# Schematic.net
KiCad netlist of a schematic drawn in EasyEDA
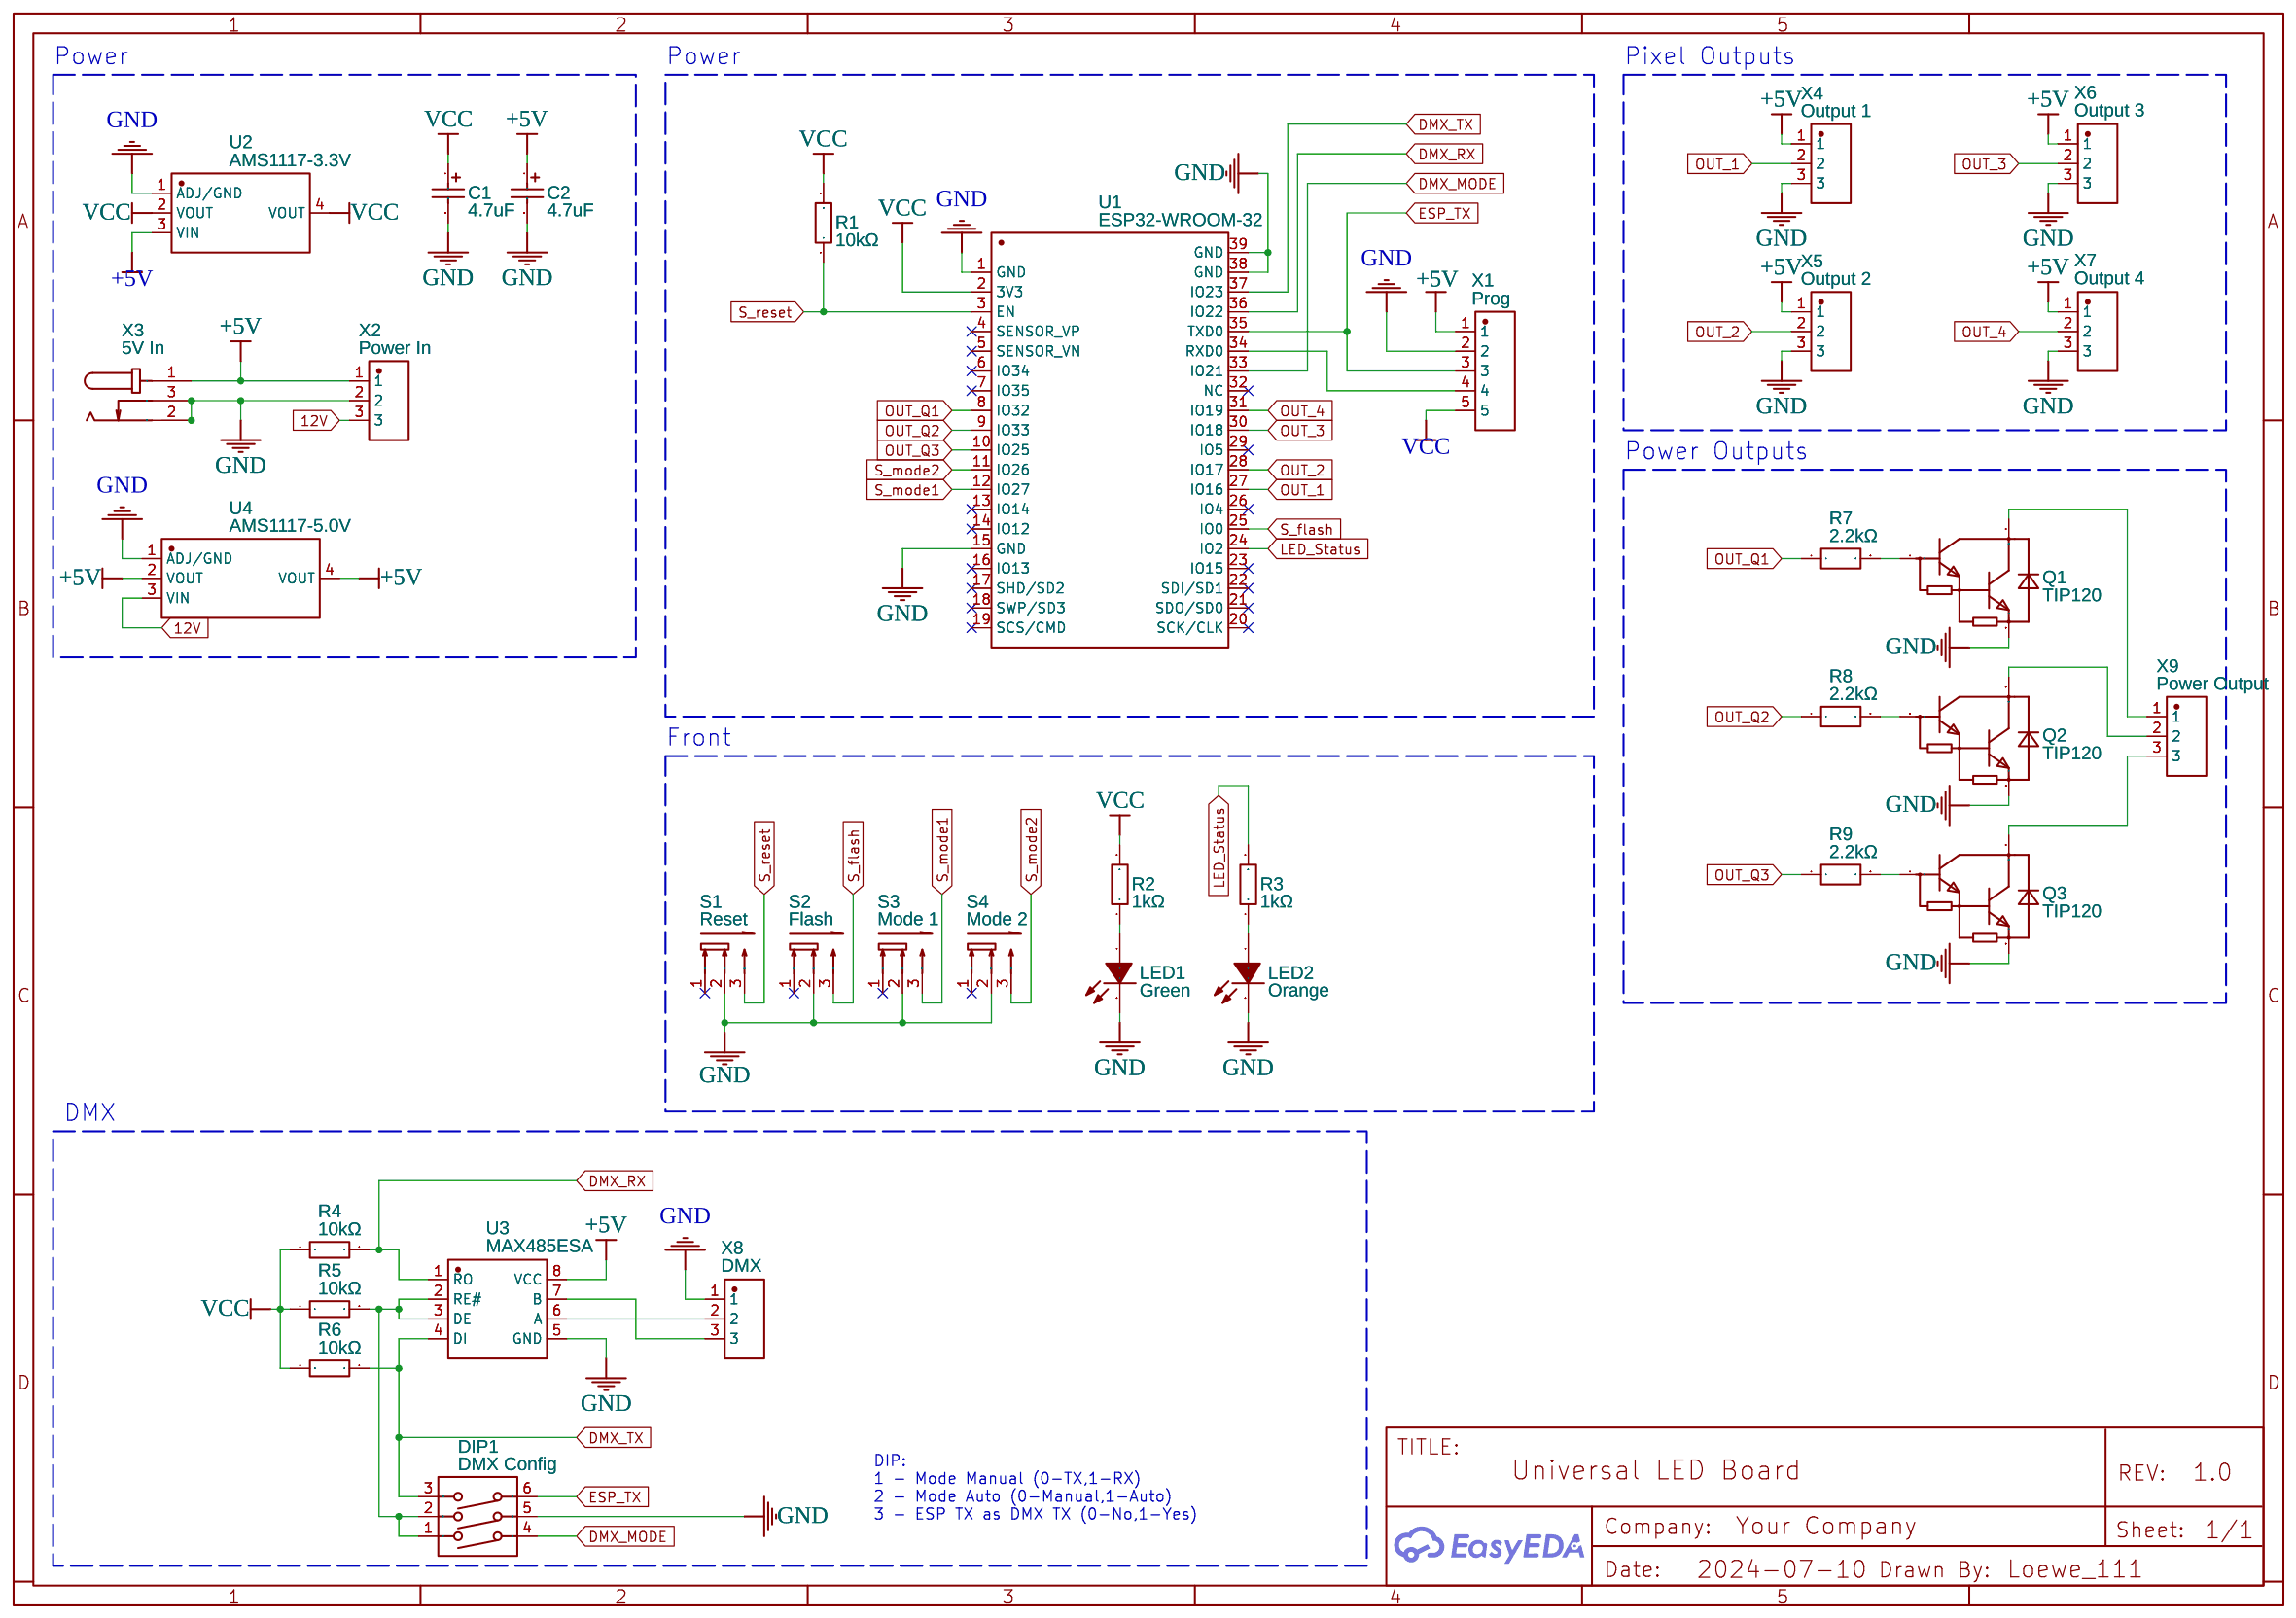
[diagram p0: schematic sheet]

(export (version "E")
  (design (tool "Eeschema 10.0.6"))
  (components
    (comp (ref "C1")
      (value "4.7uF")
      (fields
        (field (name "Manufacturer Part") "CA45-A-16V-4.7uF-K")
        (field (name "Manufacturer") "CEC(振华新云)")
      )
      (libsource (lib "") (part "CA45-A-16V-4.7UF-K"))
    )
    (comp (ref "C2")
      (value "4.7uF")
      (fields
        (field (name "Manufacturer Part") "CA45-A-16V-4.7uF-K")
        (field (name "Manufacturer") "CEC(振华新云)")
      )
      (libsource (lib "") (part "CA45-A-16V-4.7UF-K"))
    )
    (comp (ref "DIP1")
      (value "DMX Config")
      (fields (field (name "Manufacturer Part") "DSWB03LHGET") (field (name "Manufacturer") "YE"))
      (libsource (lib "") (part "DSWB03LHGET"))
    )
    (comp (ref "LED1")
      (value "Green")
      (fields (field (name "Manufacturer Part") "SZYY0603G") (field (name "Manufacturer") "yongyu(永裕光电)"))
      (libsource (lib "") (part "SZYY0603G"))
    )
    (comp (ref "LED2")
      (value "Orange")
      (fields (field (name "Manufacturer Part") "SZYY0603O") (field (name "Manufacturer") "yongyu(永裕光电)"))
      (libsource (lib "") (part "SZYY0603O"))
    )
    (comp (ref "Q1")
      (value "TIP120")
      (fields (field (name "Manufacturer") "ST(意法半导体)"))
      (libsource (lib "") (part "TIP120"))
    )
    (comp (ref "Q2")
      (value "TIP120")
      (fields (field (name "Manufacturer") "ST(意法半导体)"))
      (libsource (lib "") (part "TIP120"))
    )
    (comp (ref "Q3")
      (value "TIP120")
      (fields (field (name "Manufacturer") "ST(意法半导体)"))
      (libsource (lib "") (part "TIP120"))
    )
    (comp (ref "R1")
      (value "10kΩ")
      (fields
        (field (name "Manufacturer Part") "0603WAF1002T5E")
        (field (name "Manufacturer") "UNI-ROYAL(厚声)")
      )
      (libsource (lib "") (part "0603WAF1002T5E_2"))
    )
    (comp (ref "R2")
      (value "1kΩ")
      (fields (field (name "Manufacturer Part") "RC0603FR-071KL") (field (name "Manufacturer") "YAGEO(国巨)"))
      (libsource (lib "") (part "RC0603FR-071KL"))
    )
    (comp (ref "R3")
      (value "1kΩ")
      (fields (field (name "Manufacturer Part") "RC0603FR-071KL") (field (name "Manufacturer") "YAGEO(国巨)"))
      (libsource (lib "") (part "RC0603FR-071KL"))
    )
    (comp (ref "R4")
      (value "10kΩ")
      (fields
        (field (name "Manufacturer Part") "0603WAF1002T5E")
        (field (name "Manufacturer") "UNI-ROYAL(厚声)")
      )
      (libsource (lib "") (part "0603WAF1002T5E"))
    )
    (comp (ref "R5")
      (value "10kΩ")
      (fields
        (field (name "Manufacturer Part") "0603WAF1002T5E")
        (field (name "Manufacturer") "UNI-ROYAL(厚声)")
      )
      (libsource (lib "") (part "0603WAF1002T5E_1"))
    )
    (comp (ref "R6")
      (value "10kΩ")
      (fields
        (field (name "Manufacturer Part") "0603WAF1002T5E")
        (field (name "Manufacturer") "UNI-ROYAL(厚声)")
      )
      (libsource (lib "") (part "0603WAF1002T5E"))
    )
    (comp (ref "R7")
      (value "2.2kΩ")
      (fields (field (name "Manufacturer Part") "FRC0603J222 TS") (field (name "Manufacturer") "FOJAN(富捷)"))
      (libsource (lib "") (part "FRC0603J222 TS"))
    )
    (comp (ref "R8")
      (value "2.2kΩ")
      (fields (field (name "Manufacturer Part") "FRC0603J222 TS") (field (name "Manufacturer") "FOJAN(富捷)"))
      (libsource (lib "") (part "FRC0603J222 TS"))
    )
    (comp (ref "R9")
      (value "2.2kΩ")
      (fields (field (name "Manufacturer Part") "FRC0603J222 TS") (field (name "Manufacturer") "FOJAN(富捷)"))
      (libsource (lib "") (part "FRC0603J222 TS"))
    )
    (comp (ref "S1")
      (value "Reset")
      (fields
        (field (name "Manufacturer Part") "XKB5858-W-C")
        (field (name "Manufacturer") "XKB Connection(中国星坤)")
      )
      (libsource (lib "") (part "XKB5858-W-C"))
    )
    (comp (ref "S2")
      (value "Flash")
      (fields
        (field (name "Manufacturer Part") "XKB5858-W-C")
        (field (name "Manufacturer") "XKB Connection(中国星坤)")
      )
      (libsource (lib "") (part "XKB5858-W-C"))
    )
    (comp (ref "S3")
      (value "Mode 1")
      (fields
        (field (name "Manufacturer Part") "XKB5858-W-C")
        (field (name "Manufacturer") "XKB Connection(中国星坤)")
      )
      (libsource (lib "") (part "XKB5858-W-C"))
    )
    (comp (ref "S4")
      (value "Mode 2")
      (fields
        (field (name "Manufacturer Part") "XKB5858-W-C")
        (field (name "Manufacturer") "XKB Connection(中国星坤)")
      )
      (libsource (lib "") (part "XKB5858-W-C"))
    )
    (comp (ref "U1")
      (value "ESP32-WROOM-32")
      (fields
        (field (name "Manufacturer Part") "ESP32-WROOM-32-N4")
        (field (name "Manufacturer") "ESPRESSIF(乐鑫)")
      )
      (libsource (lib "") (part "ESP32-WROOM-32"))
    )
    (comp (ref "U2")
      (value "AMS1117-3.3V")
      (fields (field (name "Manufacturer") "WPMtek(维攀)"))
      (libsource (lib "") (part "AMS1117-3.3V"))
    )
    (comp (ref "U3")
      (value "MAX485ESA")
      (fields (field (name "Manufacturer Part") "max485ESA") (field (name "Manufacturer") "JSMSEMI(杰盛微)"))
      (libsource (lib "") (part "MAX485ESA"))
    )
    (comp (ref "U4")
      (value "AMS1117-5.0V")
      (fields (field (name "Manufacturer Part") "AMS1117-5.0") (field (name "Manufacturer") "WPMtek(维攀)"))
      (libsource (lib "") (part "AMS1117-5.0_C2909825"))
    )
    (comp (ref "X1")
      (value "Prog")
      (fields
        (field (name "Manufacturer Part") "ZX-XH2.54-5PZZ")
        (field (name "Manufacturer") "Megastar(兆星)")
      )
      (libsource (lib "") (part "ZX-XH2.54-5PZZ"))
    )
    (comp (ref "X2")
      (value "Power In")
      (fields
        (field (name "Manufacturer Part") "DB128L-5.08-3P-GN-S")
        (field (name "Manufacturer") "DORABO(地博电气)")
      )
      (libsource (lib "") (part "DB128L-5.08-3P"))
    )
    (comp (ref "X3")
      (value "5V In")
      (fields (field (name "Manufacturer Part") "DC-005-A200") (field (name "Manufacturer") "XUNPU(讯普)"))
      (libsource (lib "") (part "DC-005-A200"))
    )
    (comp (ref "X4")
      (value "Output 1")
      (fields
        (field (name "Manufacturer Part") "DB128L-5.08-3P-GN-S")
        (field (name "Manufacturer") "DORABO(地博电气)")
      )
      (libsource (lib "") (part "DB128L-5.08-3P"))
    )
    (comp (ref "X5")
      (value "Output 2")
      (fields
        (field (name "Manufacturer Part") "DB128L-5.08-3P-GN-S")
        (field (name "Manufacturer") "DORABO(地博电气)")
      )
      (libsource (lib "") (part "DB128L-5.08-3P"))
    )
    (comp (ref "X6")
      (value "Output 3")
      (fields
        (field (name "Manufacturer Part") "ZX-XH2.54-3PZZ")
        (field (name "Manufacturer") "Megastar(兆星)")
      )
      (libsource (lib "") (part "ZX-XH2.54-3PZZ"))
    )
    (comp (ref "X7")
      (value "Output 4")
      (fields
        (field (name "Manufacturer Part") "ZX-XH2.54-3PZZ")
        (field (name "Manufacturer") "Megastar(兆星)")
      )
      (libsource (lib "") (part "ZX-XH2.54-3PZZ"))
    )
    (comp (ref "X8")
      (value "DMX")
      (fields
        (field (name "Manufacturer Part") "ZX-XH2.54-3PZZ")
        (field (name "Manufacturer") "Megastar(兆星)")
      )
      (libsource (lib "") (part "ZX-XH2.54-3PZZ"))
    )
    (comp (ref "X9")
      (value "Power Output")
      (fields
        (field (name "Manufacturer Part") "DB128L-5.08-3P-GN-S")
        (field (name "Manufacturer") "DORABO(地博电气)")
      )
      (libsource (lib "") (part "DB128L-5.08-3P"))
    )
  )
  (nets
    (net (code "1") (name "+5V") (class "Default")
      (node (ref "C2") (pin "1") (pinfunction "1_1") (pintype "input"))
      (node (ref "U2") (pin "3") (pinfunction "VIN_3") (pintype "unspecified"))
      (node (ref "U3") (pin "8") (pinfunction "VCC_8") (pintype "unspecified"))
      (node (ref "U4") (pin "2") (pinfunction "VOUT_2") (pintype "unspecified"))
      (node (ref "U4") (pin "4") (pinfunction "VOUT_4") (pintype "unspecified"))
      (node (ref "X1") (pin "1") (pinfunction "1_1") (pintype "unspecified"))
      (node (ref "X2") (pin "1") (pinfunction "1_1") (pintype "unspecified"))
      (node (ref "X3") (pin "1") (pinfunction "1_1") (pintype "unspecified"))
      (node (ref "X4") (pin "1") (pinfunction "1_1") (pintype "unspecified"))
      (node (ref "X5") (pin "1") (pinfunction "1_1") (pintype "unspecified"))
      (node (ref "X6") (pin "1") (pinfunction "1_1") (pintype "unspecified"))
      (node (ref "X7") (pin "1") (pinfunction "1_1") (pintype "unspecified"))
    )
    (net (code "2") (name "12V") (class "Default")
      (node (ref "U4") (pin "3") (pinfunction "VIN_3") (pintype "unspecified"))
      (node (ref "X2") (pin "3") (pinfunction "3_3") (pintype "unspecified"))
    )
    (net (code "3") (name "DMX_MODE") (class "Default")
      (node (ref "DIP1") (pin "4") (pinfunction "4_4") (pintype "unspecified"))
      (node (ref "U1") (pin "33") (pinfunction "IO21_33") (pintype "unspecified"))
    )
    (net (code "4") (name "DMX_RX") (class "Default")
      (node (ref "R4") (pin "1") (pinfunction "1_1") (pintype "input"))
      (node (ref "U1") (pin "36") (pinfunction "IO22_36") (pintype "unspecified"))
      (node (ref "U3") (pin "1") (pinfunction "RO_1") (pintype "unspecified"))
    )
    (net (code "5") (name "DMX_TX") (class "Default")
      (node (ref "DIP1") (pin "3") (pinfunction "3_3") (pintype "unspecified"))
      (node (ref "R6") (pin "1") (pinfunction "1_1") (pintype "input"))
      (node (ref "U1") (pin "37") (pinfunction "IO23_37") (pintype "unspecified"))
      (node (ref "U3") (pin "4") (pinfunction "DI_4") (pintype "unspecified"))
    )
    (net (code "6") (name "ESP_TX") (class "Default")
      (node (ref "DIP1") (pin "6") (pinfunction "6_6") (pintype "unspecified"))
      (node (ref "U1") (pin "35") (pinfunction "TXD0_35") (pintype "unspecified"))
      (node (ref "X1") (pin "3") (pinfunction "3_3") (pintype "unspecified"))
    )
    (net (code "7") (name "GND") (class "Default")
      (node (ref "C1") (pin "2") (pinfunction "2_2") (pintype "input"))
      (node (ref "C2") (pin "2") (pinfunction "2_2") (pintype "input"))
      (node (ref "DIP1") (pin "5") (pinfunction "5_5") (pintype "unspecified"))
      (node (ref "LED1") (pin "2") (pinfunction "-_2") (pintype "unspecified"))
      (node (ref "LED2") (pin "2") (pinfunction "-_2") (pintype "unspecified"))
      (node (ref "Q1") (pin "3") (pinfunction "E_3") (pintype "input"))
      (node (ref "Q2") (pin "3") (pinfunction "E_3") (pintype "input"))
      (node (ref "Q3") (pin "3") (pinfunction "E_3") (pintype "input"))
      (node (ref "S1") (pin "2") (pinfunction "2_2") (pintype "unspecified"))
      (node (ref "S2") (pin "2") (pinfunction "2_2") (pintype "unspecified"))
      (node (ref "S3") (pin "2") (pinfunction "2_2") (pintype "unspecified"))
      (node (ref "S4") (pin "2") (pinfunction "2_2") (pintype "unspecified"))
      (node (ref "U1") (pin "1") (pinfunction "GND_1") (pintype "unspecified"))
      (node (ref "U1") (pin "15") (pinfunction "GND_15") (pintype "unspecified"))
      (node (ref "U1") (pin "38") (pinfunction "GND_38") (pintype "unspecified"))
      (node (ref "U1") (pin "39") (pinfunction "GND_39") (pintype "unspecified"))
      (node (ref "U2") (pin "1") (pinfunction "ADJ/GND_1") (pintype "unspecified"))
      (node (ref "U3") (pin "5") (pinfunction "GND_5") (pintype "unspecified"))
      (node (ref "U4") (pin "1") (pinfunction "ADJ/GND_1") (pintype "unspecified"))
      (node (ref "X1") (pin "2") (pinfunction "2_2") (pintype "unspecified"))
      (node (ref "X2") (pin "2") (pinfunction "2_2") (pintype "unspecified"))
      (node (ref "X3") (pin "2") (pinfunction "2_2") (pintype "unspecified"))
      (node (ref "X3") (pin "3") (pinfunction "3_3") (pintype "unspecified"))
      (node (ref "X4") (pin "3") (pinfunction "3_3") (pintype "unspecified"))
      (node (ref "X5") (pin "3") (pinfunction "3_3") (pintype "unspecified"))
      (node (ref "X6") (pin "3") (pinfunction "3_3") (pintype "unspecified"))
      (node (ref "X7") (pin "3") (pinfunction "3_3") (pintype "unspecified"))
      (node (ref "X8") (pin "1") (pinfunction "1_1") (pintype "unspecified"))
    )
    (net (code "8") (name "LED_Status") (class "Default")
      (node (ref "R3") (pin "2") (pinfunction "2_2") (pintype "input"))
      (node (ref "U1") (pin "24") (pinfunction "IO2_24") (pintype "unspecified"))
    )
    (net (code "9") (name "Net-(LED1-+)") (class "Default")
      (node (ref "LED1") (pin "1") (pinfunction "+_1") (pintype "unspecified"))
      (node (ref "R2") (pin "1") (pinfunction "1_1") (pintype "input"))
    )
    (net (code "10") (name "Net-(LED2-+)") (class "Default")
      (node (ref "LED2") (pin "1") (pinfunction "+_1") (pintype "unspecified"))
      (node (ref "R3") (pin "1") (pinfunction "1_1") (pintype "input"))
    )
    (net (code "11") (name "Net-(Q1-B)") (class "Default")
      (node (ref "Q1") (pin "1") (pinfunction "B_1") (pintype "input"))
      (node (ref "R7") (pin "2") (pinfunction "2_2") (pintype "unspecified"))
    )
    (net (code "12") (name "Net-(Q1-C)") (class "Default")
      (node (ref "Q1") (pin "2") (pinfunction "C_2") (pintype "input"))
      (node (ref "X9") (pin "1") (pinfunction "1_1") (pintype "unspecified"))
    )
    (net (code "13") (name "Net-(Q2-B)") (class "Default")
      (node (ref "Q2") (pin "1") (pinfunction "B_1") (pintype "input"))
      (node (ref "R8") (pin "2") (pinfunction "2_2") (pintype "unspecified"))
    )
    (net (code "14") (name "Net-(Q2-C)") (class "Default")
      (node (ref "Q2") (pin "2") (pinfunction "C_2") (pintype "input"))
      (node (ref "X9") (pin "2") (pinfunction "2_2") (pintype "unspecified"))
    )
    (net (code "15") (name "Net-(Q3-B)") (class "Default")
      (node (ref "Q3") (pin "1") (pinfunction "B_1") (pintype "input"))
      (node (ref "R9") (pin "2") (pinfunction "2_2") (pintype "unspecified"))
    )
    (net (code "16") (name "Net-(Q3-C)") (class "Default")
      (node (ref "Q3") (pin "2") (pinfunction "C_2") (pintype "input"))
      (node (ref "X9") (pin "3") (pinfunction "3_3") (pintype "unspecified"))
    )
    (net (code "17") (name "Net-(U1-RXD0)") (class "Default")
      (node (ref "U1") (pin "34") (pinfunction "RXD0_34") (pintype "unspecified"))
      (node (ref "X1") (pin "4") (pinfunction "4_4") (pintype "unspecified"))
    )
    (net (code "18") (name "Net-(U3-A)") (class "Default")
      (node (ref "U3") (pin "6") (pinfunction "A_6") (pintype "unspecified"))
      (node (ref "X8") (pin "2") (pinfunction "2_2") (pintype "unspecified"))
    )
    (net (code "19") (name "Net-(U3-B)") (class "Default")
      (node (ref "U3") (pin "7") (pinfunction "B_7") (pintype "unspecified"))
      (node (ref "X8") (pin "3") (pinfunction "3_3") (pintype "unspecified"))
    )
    (net (code "20") (name "Net-(U3-DE)") (class "Default")
      (node (ref "DIP1") (pin "1") (pinfunction "1_1") (pintype "unspecified"))
      (node (ref "DIP1") (pin "2") (pinfunction "2_2") (pintype "unspecified"))
      (node (ref "R5") (pin "2") (pinfunction "2_2") (pintype "input"))
      (node (ref "U3") (pin "2") (pinfunction "RE#_2") (pintype "unspecified"))
      (node (ref "U3") (pin "3") (pinfunction "DE_3") (pintype "unspecified"))
    )
    (net (code "21") (name "OUT_1") (class "Default")
      (node (ref "U1") (pin "27") (pinfunction "IO16_27") (pintype "unspecified"))
      (node (ref "X4") (pin "2") (pinfunction "2_2") (pintype "unspecified"))
    )
    (net (code "22") (name "OUT_2") (class "Default")
      (node (ref "U1") (pin "28") (pinfunction "IO17_28") (pintype "unspecified"))
      (node (ref "X5") (pin "2") (pinfunction "2_2") (pintype "unspecified"))
    )
    (net (code "23") (name "OUT_3") (class "Default")
      (node (ref "U1") (pin "30") (pinfunction "IO18_30") (pintype "unspecified"))
      (node (ref "X6") (pin "2") (pinfunction "2_2") (pintype "unspecified"))
    )
    (net (code "24") (name "OUT_4") (class "Default")
      (node (ref "U1") (pin "31") (pinfunction "IO19_31") (pintype "unspecified"))
      (node (ref "X7") (pin "2") (pinfunction "2_2") (pintype "unspecified"))
    )
    (net (code "25") (name "OUT_Q1") (class "Default")
      (node (ref "R7") (pin "1") (pinfunction "1_1") (pintype "unspecified"))
      (node (ref "U1") (pin "8") (pinfunction "IO32_8") (pintype "unspecified"))
    )
    (net (code "26") (name "OUT_Q2") (class "Default")
      (node (ref "R8") (pin "1") (pinfunction "1_1") (pintype "unspecified"))
      (node (ref "U1") (pin "9") (pinfunction "IO33_9") (pintype "unspecified"))
    )
    (net (code "27") (name "OUT_Q3") (class "Default")
      (node (ref "R9") (pin "1") (pinfunction "1_1") (pintype "unspecified"))
      (node (ref "U1") (pin "10") (pinfunction "IO25_10") (pintype "unspecified"))
    )
    (net (code "28") (name "S_flash") (class "Default")
      (node (ref "S2") (pin "3") (pinfunction "3_3") (pintype "unspecified"))
      (node (ref "U1") (pin "25") (pinfunction "IO0_25") (pintype "unspecified"))
    )
    (net (code "29") (name "S_mode1") (class "Default")
      (node (ref "S3") (pin "3") (pinfunction "3_3") (pintype "unspecified"))
      (node (ref "U1") (pin "12") (pinfunction "IO27_12") (pintype "unspecified"))
    )
    (net (code "30") (name "S_mode2") (class "Default")
      (node (ref "S4") (pin "3") (pinfunction "3_3") (pintype "unspecified"))
      (node (ref "U1") (pin "11") (pinfunction "IO26_11") (pintype "unspecified"))
    )
    (net (code "31") (name "S_reset") (class "Default")
      (node (ref "R1") (pin "1") (pinfunction "1_1") (pintype "input"))
      (node (ref "S1") (pin "3") (pinfunction "3_3") (pintype "unspecified"))
      (node (ref "U1") (pin "3") (pinfunction "EN_3") (pintype "unspecified"))
    )
    (net (code "32") (name "VCC") (class "Default")
      (node (ref "C1") (pin "1") (pinfunction "1_1") (pintype "input"))
      (node (ref "R1") (pin "2") (pinfunction "2_2") (pintype "input"))
      (node (ref "R2") (pin "2") (pinfunction "2_2") (pintype "input"))
      (node (ref "R4") (pin "2") (pinfunction "2_2") (pintype "input"))
      (node (ref "R5") (pin "1") (pinfunction "1_1") (pintype "input"))
      (node (ref "R6") (pin "2") (pinfunction "2_2") (pintype "input"))
      (node (ref "U1") (pin "2") (pinfunction "3V3_2") (pintype "unspecified"))
      (node (ref "U2") (pin "2") (pinfunction "VOUT_2") (pintype "unspecified"))
      (node (ref "U2") (pin "4") (pinfunction "VOUT_4") (pintype "unspecified"))
      (node (ref "X1") (pin "5") (pinfunction "5_5") (pintype "unspecified"))
    )
    (net (code "33") (name "unconnected-(S1-Pad1)") (class "Default")
      (node (ref "S1") (pin "1") (pinfunction "1_1") (pintype "unspecified+no_connect"))
    )
    (net (code "34") (name "unconnected-(S2-Pad1)") (class "Default")
      (node (ref "S2") (pin "1") (pinfunction "1_1") (pintype "unspecified+no_connect"))
    )
    (net (code "35") (name "unconnected-(S3-Pad1)") (class "Default")
      (node (ref "S3") (pin "1") (pinfunction "1_1") (pintype "unspecified+no_connect"))
    )
    (net (code "36") (name "unconnected-(S4-Pad1)") (class "Default")
      (node (ref "S4") (pin "1") (pinfunction "1_1") (pintype "unspecified+no_connect"))
    )
    (net (code "37") (name "unconnected-(U1-IO4-Pad26)") (class "Default")
      (node (ref "U1") (pin "26") (pinfunction "IO4_26") (pintype "unspecified+no_connect"))
    )
    (net (code "38") (name "unconnected-(U1-IO5-Pad29)") (class "Default")
      (node (ref "U1") (pin "29") (pinfunction "IO5_29") (pintype "unspecified+no_connect"))
    )
    (net (code "39") (name "unconnected-(U1-IO12-Pad14)") (class "Default")
      (node (ref "U1") (pin "14") (pinfunction "IO12_14") (pintype "unspecified+no_connect"))
    )
    (net (code "40") (name "unconnected-(U1-IO13-Pad16)") (class "Default")
      (node (ref "U1") (pin "16") (pinfunction "IO13_16") (pintype "unspecified+no_connect"))
    )
    (net (code "41") (name "unconnected-(U1-IO14-Pad13)") (class "Default")
      (node (ref "U1") (pin "13") (pinfunction "IO14_13") (pintype "unspecified+no_connect"))
    )
    (net (code "42") (name "unconnected-(U1-IO15-Pad23)") (class "Default")
      (node (ref "U1") (pin "23") (pinfunction "IO15_23") (pintype "unspecified+no_connect"))
    )
    (net (code "43") (name "unconnected-(U1-IO34-Pad6)") (class "Default")
      (node (ref "U1") (pin "6") (pinfunction "IO34_6") (pintype "unspecified+no_connect"))
    )
    (net (code "44") (name "unconnected-(U1-IO35-Pad7)") (class "Default")
      (node (ref "U1") (pin "7") (pinfunction "IO35_7") (pintype "unspecified+no_connect"))
    )
    (net (code "45") (name "unconnected-(U1-NC-Pad32)") (class "Default")
      (node (ref "U1") (pin "32") (pinfunction "NC_32") (pintype "unspecified+no_connect"))
    )
    (net (code "46") (name "unconnected-(U1-SCK{slash}CLK-Pad20)") (class "Default")
      (node (ref "U1") (pin "20") (pinfunction "SCK/CLK_20") (pintype "unspecified+no_connect"))
    )
    (net (code "47") (name "unconnected-(U1-SCS{slash}CMD-Pad19)") (class "Default")
      (node (ref "U1") (pin "19") (pinfunction "SCS/CMD_19") (pintype "unspecified+no_connect"))
    )
    (net (code "48") (name "unconnected-(U1-SDI{slash}SD1-Pad22)") (class "Default")
      (node (ref "U1") (pin "22") (pinfunction "SDI/SD1_22") (pintype "unspecified+no_connect"))
    )
    (net (code "49") (name "unconnected-(U1-SDO{slash}SD0-Pad21)") (class "Default")
      (node (ref "U1") (pin "21") (pinfunction "SDO/SD0_21") (pintype "unspecified+no_connect"))
    )
    (net (code "50") (name "unconnected-(U1-SENSOR_VN-Pad5)") (class "Default")
      (node (ref "U1") (pin "5") (pinfunction "SENSOR_VN_5") (pintype "unspecified+no_connect"))
    )
    (net (code "51") (name "unconnected-(U1-SENSOR_VP-Pad4)") (class "Default")
      (node (ref "U1") (pin "4") (pinfunction "SENSOR_VP_4") (pintype "unspecified+no_connect"))
    )
    (net (code "52") (name "unconnected-(U1-SHD{slash}SD2-Pad17)") (class "Default")
      (node (ref "U1") (pin "17") (pinfunction "SHD/SD2_17") (pintype "unspecified+no_connect"))
    )
    (net (code "53") (name "unconnected-(U1-SWP{slash}SD3-Pad18)") (class "Default")
      (node (ref "U1") (pin "18") (pinfunction "SWP/SD3_18") (pintype "unspecified+no_connect"))
    )
  )
)
